# BATTERY.net
KiCad netlist of a schematic drawn in Altium Designer
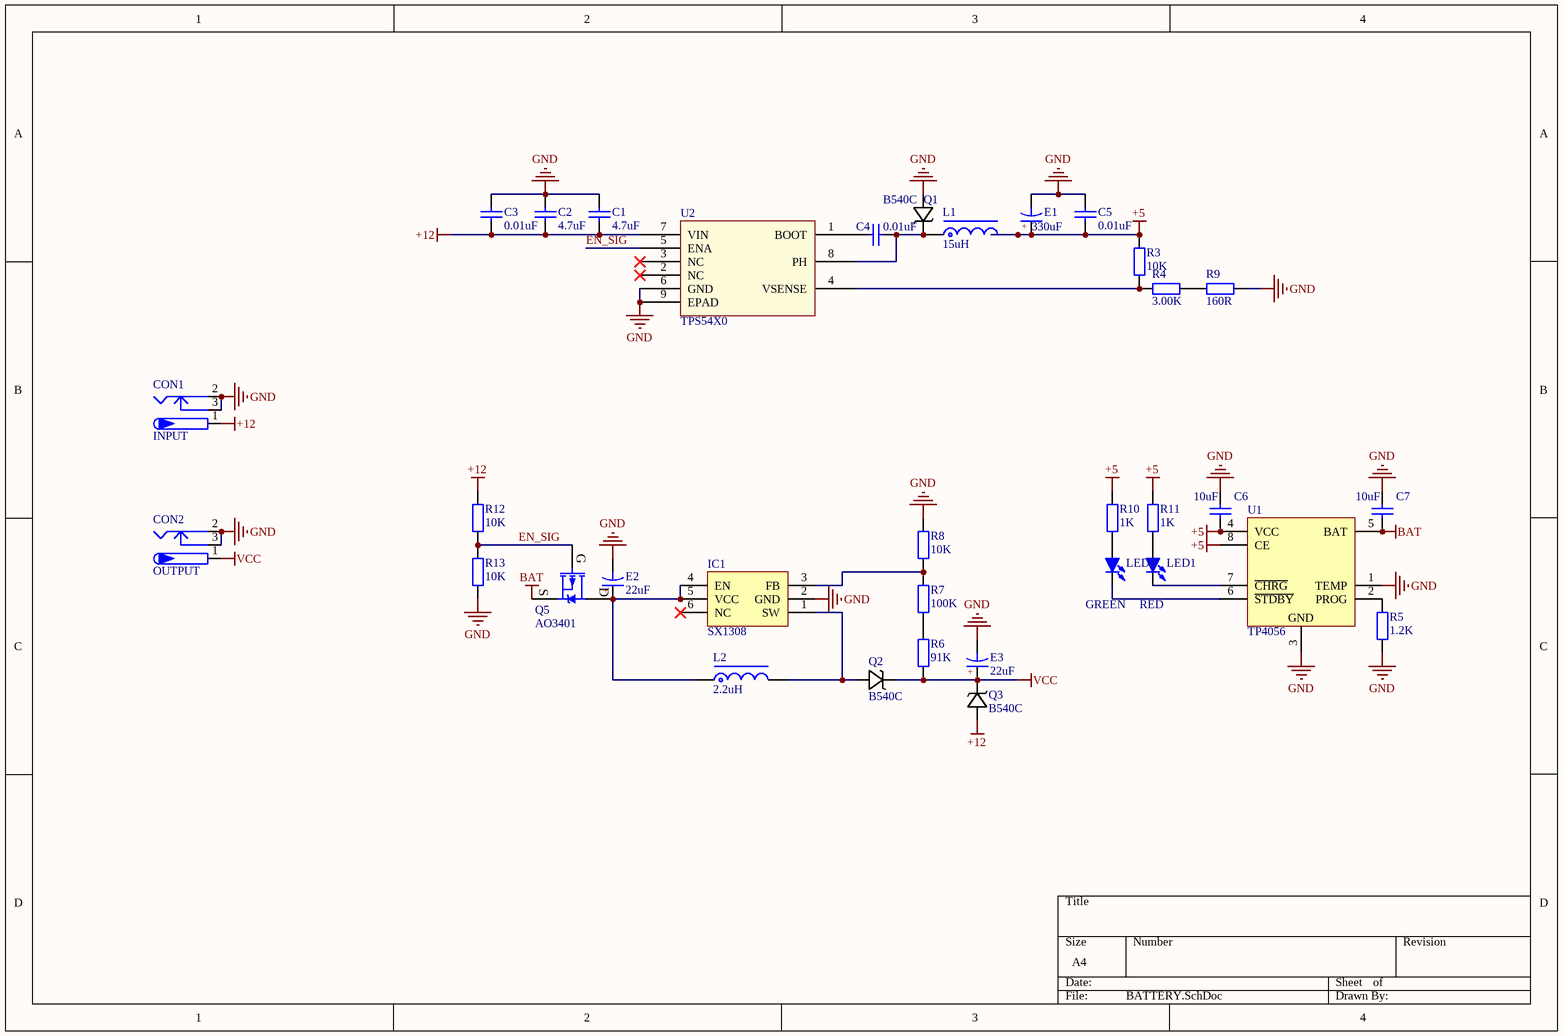
[diagram p0: BATTERY.SchDoc]

(export (version "E")
  (design (tool "Eeschema 10.0.6"))
  (components
    (comp (ref "C1")
      (value "4.7uF")
      (footprint "C0603_M")
      (description "贴片电容/MLCC电容")
      (libsource (lib "0.1 - 电阻-电容-电感-晶振-晶体-磁珠-电位器-法拉电容-馈通电容") (part "C"))
    )
    (comp (ref "C2")
      (value "4.7uF")
      (footprint "C0603_M")
      (description "贴片电容/MLCC电容")
      (libsource (lib "0.1 - 电阻-电容-电感-晶振-晶体-磁珠-电位器-法拉电容-馈通电容") (part "C"))
    )
    (comp (ref "C3")
      (value "0.01uF")
      (footprint "C0603_M")
      (description "贴片电容/MLCC电容")
      (libsource (lib "0.1 - 电阻-电容-电感-晶振-晶体-磁珠-电位器-法拉电容-馈通电容") (part "C"))
    )
    (comp (ref "C4")
      (value "0.01uF")
      (footprint "C0603_M")
      (description "贴片电容/MLCC电容")
      (libsource (lib "0.1 - 电阻-电容-电感-晶振-晶体-磁珠-电位器-法拉电容-馈通电容") (part "C"))
    )
    (comp (ref "C5")
      (value "0.01uF")
      (footprint "C0603_M")
      (description "贴片电容/MLCC电容")
      (libsource (lib "0.1 - 电阻-电容-电感-晶振-晶体-磁珠-电位器-法拉电容-馈通电容") (part "C"))
    )
    (comp (ref "C6")
      (value "10uF")
      (footprint "C0603_M")
      (description "贴片电容/MLCC电容")
      (libsource (lib "0.1 - 电阻-电容-电感-晶振-晶体-磁珠-电位器-法拉电容-馈通电容") (part "C"))
    )
    (comp (ref "C7")
      (value "10uF")
      (footprint "C0603_M")
      (description "贴片电容/MLCC电容")
      (libsource (lib "0.1 - 电阻-电容-电感-晶振-晶体-磁珠-电位器-法拉电容-馈通电容") (part "C"))
    )
    (comp (ref "CON1")
      (value "INPUT")
      (footprint "DC-005")
      (description "低压电源接口")
      (libsource (lib "0.6 - 电源_RJ45以太网_音频_SD-TF_SIM_ USB Type-C_HDMI插座") (part "P-DC"))
    )
    (comp (ref "CON2")
      (value "OUTPUT")
      (footprint "DC-005")
      (description "低压电源接口")
      (libsource (lib "0.6 - 电源_RJ45以太网_音频_SD-TF_SIM_ USB Type-C_HDMI插座") (part "P-DC"))
    )
    (comp (ref "E1")
      (value "330uF")
      (footprint "CE D(6.3*7.7)")
      (description "贴片电解电容")
      (libsource (lib "0.1 - 电阻-电容-电感-晶振-晶体-磁珠-电位器-法拉电容-馈通电容") (part "CE_SMD"))
    )
    (comp (ref "E2")
      (value "22uF")
      (footprint "CE D(6.3*7.7)")
      (description "贴片电解电容")
      (libsource (lib "0.1 - 电阻-电容-电感-晶振-晶体-磁珠-电位器-法拉电容-馈通电容") (part "CE_SMD"))
    )
    (comp (ref "E3")
      (value "22uF")
      (footprint "CE D(6.3*7.7)")
      (description "贴片电解电容")
      (libsource (lib "0.1 - 电阻-电容-电感-晶振-晶体-磁珠-电位器-法拉电容-馈通电容") (part "CE_SMD"))
    )
    (comp (ref "IC1")
      (value "SX1308")
      (footprint "SOT23-6N")
      (description "可调2A升压芯片")
      (libsource (lib "0.7 - 电源类芯片") (part "SX1308"))
    )
    (comp (ref "L1")
      (value "15uH")
      (footprint "L-SMD-0420")
      (description "一体成型电感")
      (libsource (lib "0.1 - 电阻-电容-电感-晶振-晶体-磁珠-电位器-法拉电容-馈通电容") (part "L-Molding Choke"))
    )
    (comp (ref "L2")
      (value "2.2uH")
      (footprint "L-SMD-0420")
      (description "一体成型电感")
      (libsource (lib "0.1 - 电阻-电容-电感-晶振-晶体-磁珠-电位器-法拉电容-馈通电容") (part "L-Molding Choke"))
    )
    (comp (ref "LED1")
      (value "RED")
      (footprint "LED0805_G")
      (description "贴片LED")
      (libsource (lib "0.3 - LED发光二极管-IR二极管_接收管-光耦") (part "LED-SMD"))
    )
    (comp (ref "LED2")
      (value "GREEN")
      (footprint "LED0805_G")
      (description "贴片LED")
      (libsource (lib "0.3 - LED发光二极管-IR二极管_接收管-光耦") (part "LED-SMD"))
    )
    (comp (ref "Q1") (value "B540C") (footprint "DO-214AB") (libsource (lib "MYLIB") (part "B540X")))
    (comp (ref "Q2") (value "B540C") (footprint "DO-214AB") (libsource (lib "MYLIB") (part "B540X")))
    (comp (ref "Q3") (value "B540C") (footprint "DO-214AB") (libsource (lib "MYLIB") (part "B540X")))
    (comp (ref "Q5")
      (value "AO3401")
      (footprint "SOT23-3N")
      (description "P沟道 30V/4.2A")
      (libsource (lib "0.4 - 三极管-场效应管-可控硅") (part "AO3401"))
    )
    (comp (ref "R3")
      (value "10K")
      (footprint "R0603_M")
      (description "贴片电阻")
      (libsource (lib "0.1 - 电阻-电容-电感-晶振-晶体-磁珠-电位器-法拉电容-馈通电容") (part "R"))
    )
    (comp (ref "R4")
      (value "3.00K")
      (footprint "R0603_M")
      (description "贴片电阻")
      (libsource (lib "0.1 - 电阻-电容-电感-晶振-晶体-磁珠-电位器-法拉电容-馈通电容") (part "R"))
    )
    (comp (ref "R5")
      (value "1.2K")
      (footprint "R0603_M")
      (description "贴片电阻")
      (libsource (lib "0.1 - 电阻-电容-电感-晶振-晶体-磁珠-电位器-法拉电容-馈通电容") (part "R"))
    )
    (comp (ref "R6")
      (value "91K")
      (footprint "R0603_M")
      (description "贴片电阻")
      (libsource (lib "0.1 - 电阻-电容-电感-晶振-晶体-磁珠-电位器-法拉电容-馈通电容") (part "R"))
    )
    (comp (ref "R7")
      (value "100K")
      (footprint "R0603_M")
      (description "贴片电阻")
      (libsource (lib "0.1 - 电阻-电容-电感-晶振-晶体-磁珠-电位器-法拉电容-馈通电容") (part "R"))
    )
    (comp (ref "R8")
      (value "10K")
      (footprint "R0603_M")
      (description "贴片电阻")
      (libsource (lib "0.1 - 电阻-电容-电感-晶振-晶体-磁珠-电位器-法拉电容-馈通电容") (part "R"))
    )
    (comp (ref "R9")
      (value "160R")
      (footprint "R0603_M")
      (description "贴片电阻")
      (libsource (lib "0.1 - 电阻-电容-电感-晶振-晶体-磁珠-电位器-法拉电容-馈通电容") (part "R"))
    )
    (comp (ref "R10")
      (value "1K")
      (footprint "R0603_M")
      (description "贴片电阻")
      (libsource (lib "0.1 - 电阻-电容-电感-晶振-晶体-磁珠-电位器-法拉电容-馈通电容") (part "R"))
    )
    (comp (ref "R11")
      (value "1K")
      (footprint "R0603_M")
      (description "贴片电阻")
      (libsource (lib "0.1 - 电阻-电容-电感-晶振-晶体-磁珠-电位器-法拉电容-馈通电容") (part "R"))
    )
    (comp (ref "R12")
      (value "10K")
      (footprint "R0603_M")
      (description "贴片电阻")
      (libsource (lib "0.1 - 电阻-电容-电感-晶振-晶体-磁珠-电位器-法拉电容-馈通电容") (part "R"))
    )
    (comp (ref "R13")
      (value "10K")
      (footprint "R0603_M")
      (description "贴片电阻")
      (libsource (lib "0.1 - 电阻-电容-电感-晶振-晶体-磁珠-电位器-法拉电容-馈通电容") (part "R"))
    )
    (comp (ref "U1")
      (value "TP4056")
      (footprint "SOIC-8_EP")
      (description "锂电池充电管理")
      (libsource (lib "0.8 - 常见芯片") (part "TP4056"))
    )
    (comp (ref "U2") (value "TPS54X0") (footprint "SOIC-8_EP") (libsource (lib "MYLIB") (part "TPS5450")))
  )
  (nets
    (net (code "1") (name "+5") (class "Default")
      (node (ref "C5") (pin "2") (pinfunction "2_2") (pintype "passive"))
      (node (ref "C6") (pin "2") (pinfunction "2_2") (pintype "passive"))
      (node (ref "E1") (pin "1") (pinfunction "1_1") (pintype "passive"))
      (node (ref "L1") (pin "2") (pinfunction "2_2") (pintype "passive"))
      (node (ref "R10") (pin "1") (pinfunction "1_1") (pintype "passive"))
      (node (ref "R11") (pin "1") (pinfunction "1_1") (pintype "passive"))
      (node (ref "R3") (pin "2") (pinfunction "2_2") (pintype "passive"))
      (node (ref "U1") (pin "4") (pinfunction "VCC_4") (pintype "passive"))
      (node (ref "U1") (pin "8") (pinfunction "CE_8") (pintype "passive"))
    )
    (net (code "2") (name "+12") (class "Default")
      (node (ref "C1") (pin "2") (pinfunction "2_2") (pintype "passive"))
      (node (ref "C2") (pin "2") (pinfunction "2_2") (pintype "passive"))
      (node (ref "C3") (pin "2") (pinfunction "2_2") (pintype "passive"))
      (node (ref "CON1") (pin "1") (pintype "power_in"))
      (node (ref "Q3") (pin "1") (pinfunction "1_1") (pintype "passive"))
      (node (ref "R12") (pin "1") (pinfunction "1_1") (pintype "passive"))
      (node (ref "U2") (pin "7") (pinfunction "VIN_7") (pintype "passive"))
    )
    (net (code "3") (name "/EN_SIG") (class "Default")
      (node (ref "Q5") (pin "1") (pinfunction "G_1") (pintype "passive"))
      (node (ref "R12") (pin "2") (pinfunction "2_2") (pintype "passive"))
      (node (ref "R13") (pin "1") (pinfunction "1_1") (pintype "passive"))
      (node (ref "U2") (pin "5") (pinfunction "ENA_5") (pintype "passive"))
    )
    (net (code "4") (name "BAT") (class "Default")
      (node (ref "C7") (pin "2") (pinfunction "2_2") (pintype "passive"))
      (node (ref "Q5") (pin "2") (pinfunction "S_2") (pintype "passive"))
      (node (ref "U1") (pin "5") (pinfunction "BAT_5") (pintype "passive"))
    )
    (net (code "5") (name "GND") (class "Default")
      (node (ref "C1") (pin "1") (pinfunction "1_1") (pintype "passive"))
      (node (ref "C2") (pin "1") (pinfunction "1_1") (pintype "passive"))
      (node (ref "C3") (pin "1") (pinfunction "1_1") (pintype "passive"))
      (node (ref "C5") (pin "1") (pinfunction "1_1") (pintype "passive"))
      (node (ref "C6") (pin "1") (pinfunction "1_1") (pintype "passive"))
      (node (ref "C7") (pin "1") (pinfunction "1_1") (pintype "passive"))
      (node (ref "CON1") (pin "2") (pintype "power_in"))
      (node (ref "CON1") (pin "3") (pintype "power_in"))
      (node (ref "CON2") (pin "2") (pintype "power_in"))
      (node (ref "CON2") (pin "3") (pintype "power_in"))
      (node (ref "E1") (pin "2") (pinfunction "2_2") (pintype "passive"))
      (node (ref "E2") (pin "2") (pinfunction "2_2") (pintype "passive"))
      (node (ref "E3") (pin "2") (pinfunction "2_2") (pintype "passive"))
      (node (ref "IC1") (pin "2") (pinfunction "GND_2") (pintype "passive"))
      (node (ref "Q1") (pin "1") (pinfunction "1_1") (pintype "passive"))
      (node (ref "R13") (pin "2") (pinfunction "2_2") (pintype "passive"))
      (node (ref "R5") (pin "1") (pinfunction "1_1") (pintype "passive"))
      (node (ref "R8") (pin "2") (pinfunction "2_2") (pintype "passive"))
      (node (ref "R9") (pin "1") (pinfunction "1_1") (pintype "passive"))
      (node (ref "U1") (pin "1") (pinfunction "TEMP_1") (pintype "passive"))
      (node (ref "U1") (pin "3") (pinfunction "GND_3") (pintype "passive"))
      (node (ref "U2") (pin "6") (pinfunction "GND_6") (pintype "passive"))
      (node (ref "U2") (pin "9") (pinfunction "EPAD_9") (pintype "passive"))
    )
    (net (code "6") (name "Net-(IC1-EN)") (class "Default")
      (node (ref "E2") (pin "1") (pinfunction "1_1") (pintype "passive"))
      (node (ref "IC1") (pin "4") (pinfunction "EN_4") (pintype "passive"))
      (node (ref "IC1") (pin "5") (pinfunction "VCC_5") (pintype "passive"))
      (node (ref "L2") (pin "1") (pinfunction "1_1") (pintype "passive"))
      (node (ref "Q5") (pin "3") (pinfunction "D_3") (pintype "passive"))
    )
    (net (code "7") (name "Net-(IC1-FB)") (class "Default")
      (node (ref "IC1") (pin "3") (pinfunction "FB_3") (pintype "passive"))
      (node (ref "R7") (pin "2") (pinfunction "2_2") (pintype "passive"))
      (node (ref "R8") (pin "1") (pinfunction "1_1") (pintype "passive"))
    )
    (net (code "8") (name "Net-(IC1-SW)") (class "Default")
      (node (ref "IC1") (pin "1") (pinfunction "SW_1") (pintype "passive"))
      (node (ref "L2") (pin "2") (pinfunction "2_2") (pintype "passive"))
      (node (ref "Q2") (pin "1") (pinfunction "1_1") (pintype "passive"))
    )
    (net (code "9") (name "Net-(LED1-A)") (class "Default")
      (node (ref "LED1") (pin "1") (pinfunction "A_1") (pintype "passive"))
      (node (ref "R11") (pin "2") (pinfunction "2_2") (pintype "passive"))
    )
    (net (code "10") (name "Net-(LED1-K)") (class "Default")
      (node (ref "LED1") (pin "2") (pinfunction "K_2") (pintype "passive"))
      (node (ref "U1") (pin "7") (pinfunction "~{CHRG}_7") (pintype "passive"))
    )
    (net (code "11") (name "Net-(LED2-A)") (class "Default")
      (node (ref "LED2") (pin "1") (pinfunction "A_1") (pintype "passive"))
      (node (ref "R10") (pin "2") (pinfunction "2_2") (pintype "passive"))
    )
    (net (code "12") (name "Net-(LED2-K)") (class "Default")
      (node (ref "LED2") (pin "2") (pinfunction "K_2") (pintype "passive"))
      (node (ref "U1") (pin "6") (pinfunction "~{STDBY}_6") (pintype "passive"))
    )
    (net (code "13") (name "Net-(R4-Pad1)") (class "Default")
      (node (ref "R4") (pin "1") (pinfunction "1_1") (pintype "passive"))
      (node (ref "R9") (pin "2") (pinfunction "2_2") (pintype "passive"))
    )
    (net (code "14") (name "Net-(R6-Pad2)") (class "Default")
      (node (ref "R6") (pin "2") (pinfunction "2_2") (pintype "passive"))
      (node (ref "R7") (pin "1") (pinfunction "1_1") (pintype "passive"))
    )
    (net (code "15") (name "Net-(U1-PROG)") (class "Default")
      (node (ref "R5") (pin "2") (pinfunction "2_2") (pintype "passive"))
      (node (ref "U1") (pin "2") (pinfunction "PROG_2") (pintype "passive"))
    )
    (net (code "16") (name "Net-(U2-BOOT)") (class "Default")
      (node (ref "C4") (pin "1") (pinfunction "1_1") (pintype "passive"))
      (node (ref "U2") (pin "1") (pinfunction "BOOT_1") (pintype "passive"))
    )
    (net (code "17") (name "Net-(U2-PH)") (class "Default")
      (node (ref "C4") (pin "2") (pinfunction "2_2") (pintype "passive"))
      (node (ref "L1") (pin "1") (pinfunction "1_1") (pintype "passive"))
      (node (ref "Q1") (pin "2") (pinfunction "2_2") (pintype "passive"))
      (node (ref "U2") (pin "8") (pinfunction "PH_8") (pintype "passive"))
    )
    (net (code "18") (name "Net-(U2-VSENSE)") (class "Default")
      (node (ref "R3") (pin "1") (pinfunction "1_1") (pintype "passive"))
      (node (ref "R4") (pin "2") (pinfunction "2_2") (pintype "passive"))
      (node (ref "U2") (pin "4") (pinfunction "VSENSE_4") (pintype "passive"))
    )
    (net (code "19") (name "VCC") (class "Default")
      (node (ref "CON2") (pin "1") (pintype "power_in"))
      (node (ref "E3") (pin "1") (pinfunction "1_1") (pintype "passive"))
      (node (ref "Q2") (pin "2") (pinfunction "2_2") (pintype "passive"))
      (node (ref "Q3") (pin "2") (pinfunction "2_2") (pintype "passive"))
      (node (ref "R6") (pin "1") (pinfunction "1_1") (pintype "passive"))
    )
    (net (code "20") (name "unconnected-(IC1-NC-Pad6)") (class "Default")
      (node (ref "IC1") (pin "6") (pinfunction "NC_6") (pintype "passive+no_connect"))
    )
    (net (code "21") (name "unconnected-(U2-NC-Pad2)") (class "Default")
      (node (ref "U2") (pin "2") (pinfunction "NC_2") (pintype "passive+no_connect"))
    )
    (net (code "22") (name "unconnected-(U2-NC-Pad3)") (class "Default")
      (node (ref "U2") (pin "3") (pinfunction "NC_3") (pintype "passive+no_connect"))
    )
  )
)
